# Controller.net
KiCad netlist of a schematic drawn in Altium Designer
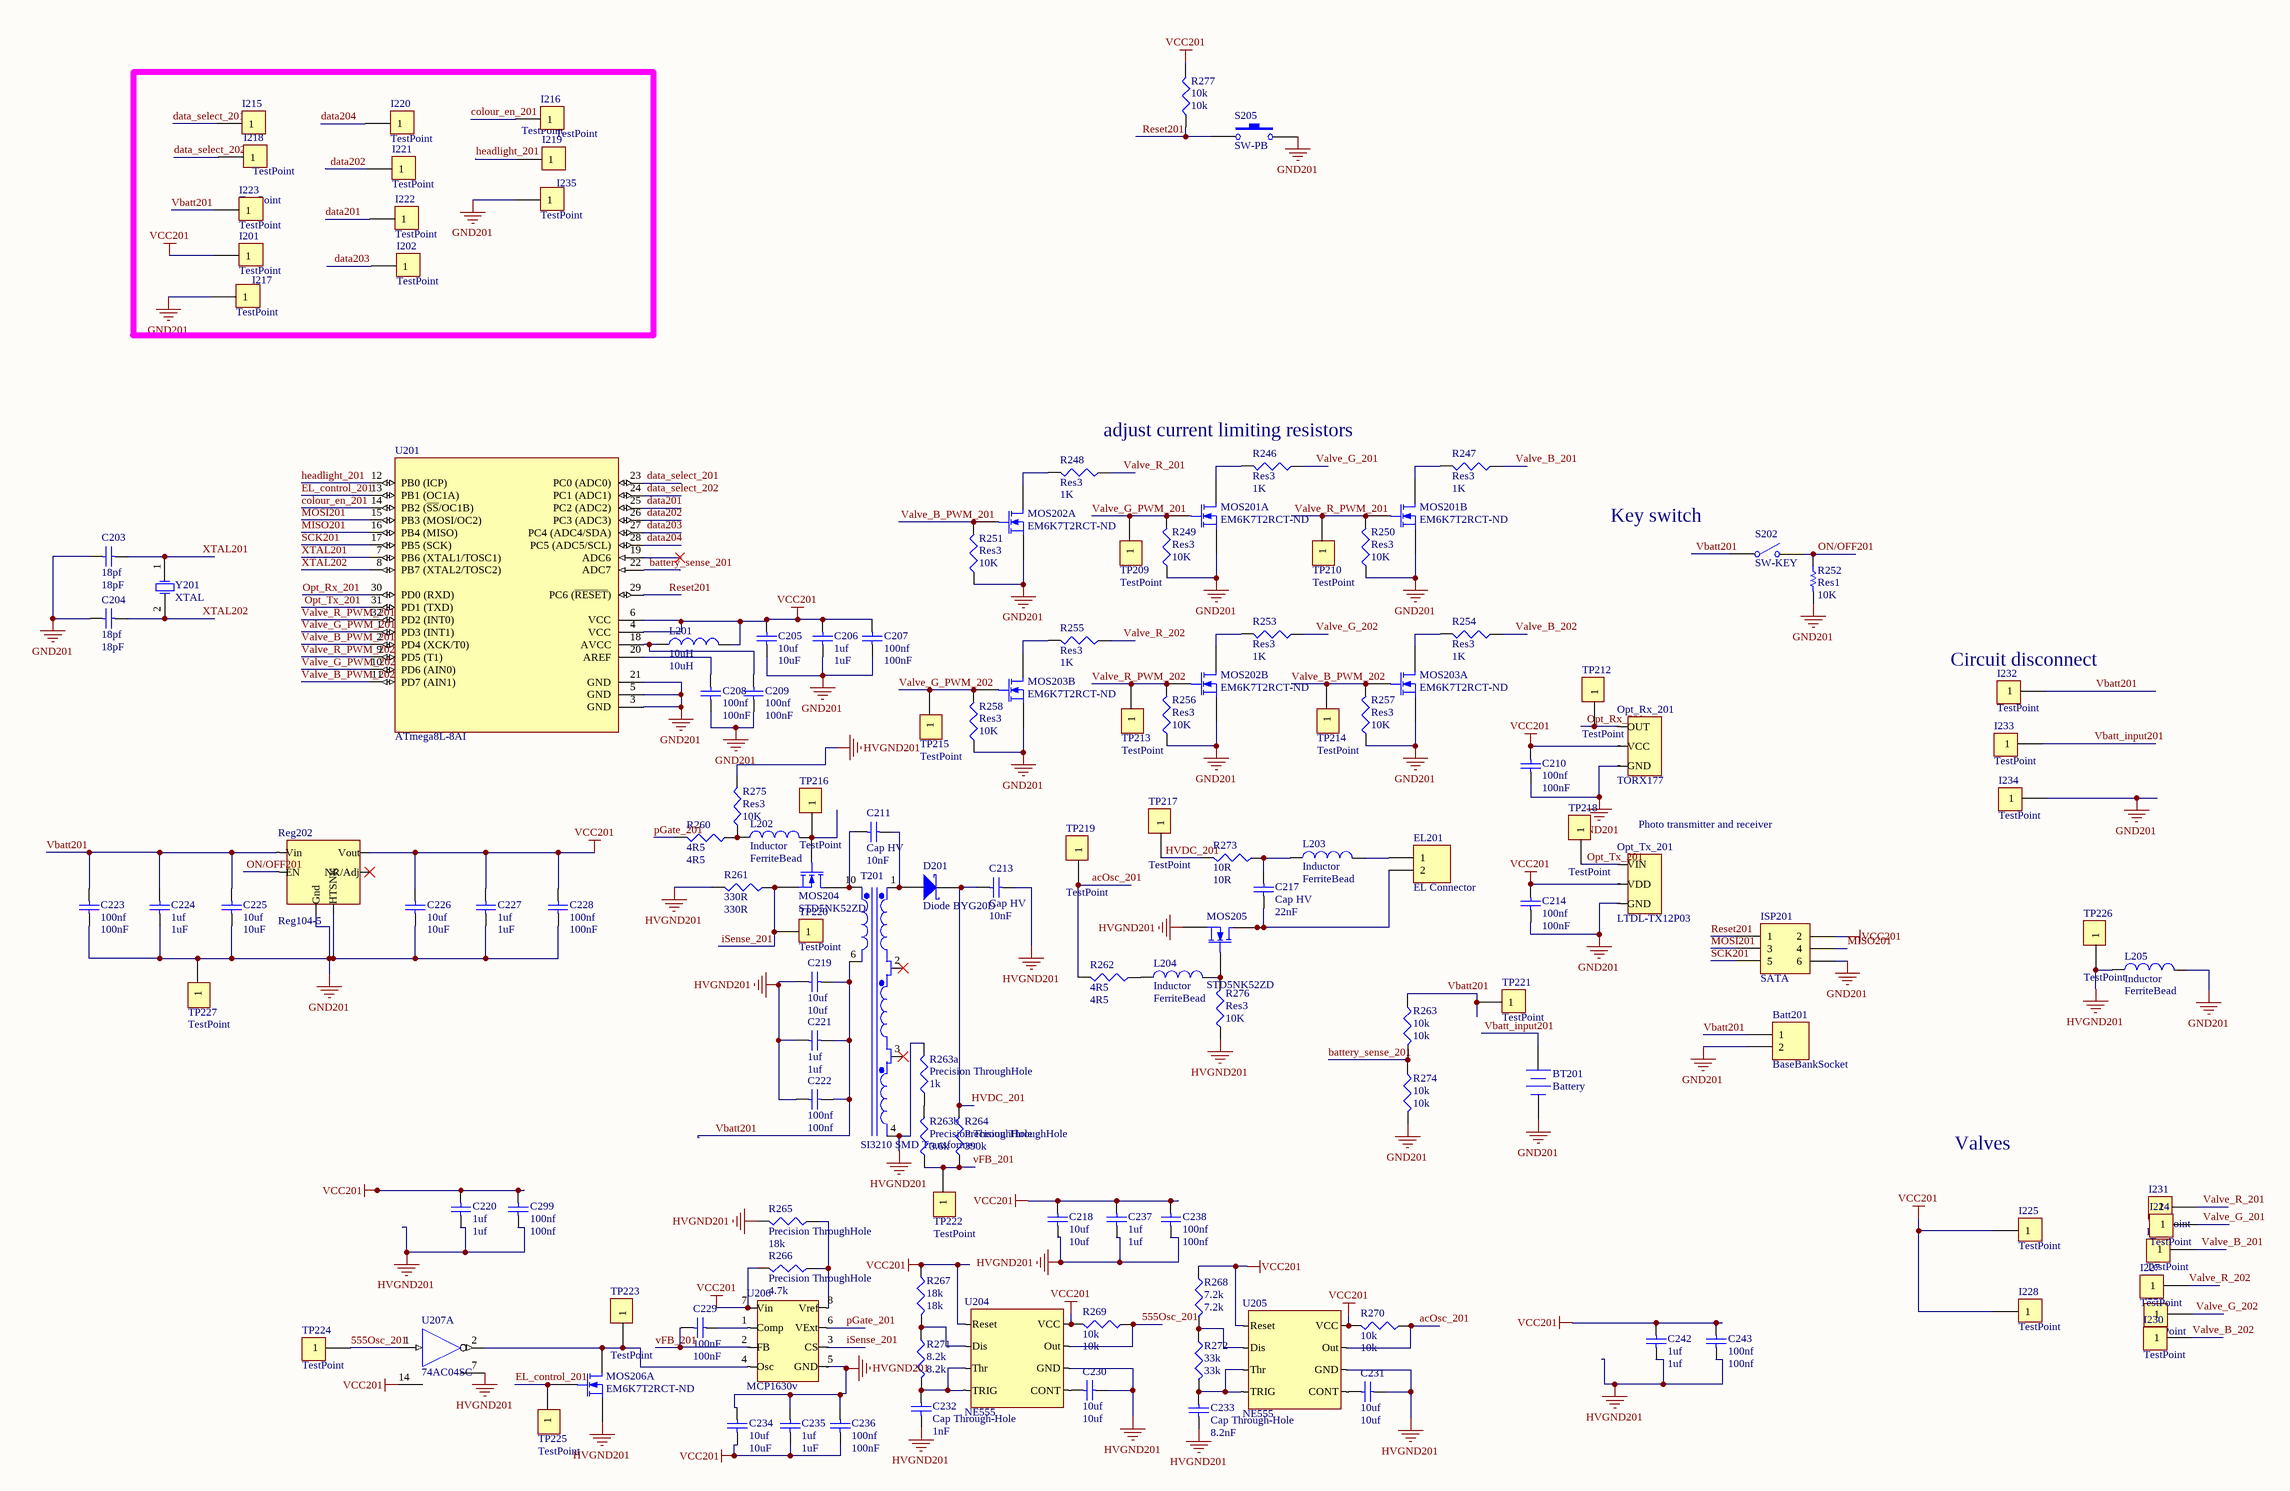
[diagram p0: Controller.SchDoc]

(export (version "E")
  (design (tool "Eeschema 10.0.6"))
  (components
    (comp (ref "Batt201")
      (value "BaseBankSocket")
      (footprint "HDR1X2H")
      (description "Header, 2-Pin")
      (libsource (lib "Miscellaneous Connectors") (part "Header 2"))
    )
    (comp (ref "BT201")
      (value "Battery")
      (footprint "HDR1X2H")
      (description "Multicell Battery")
      (libsource (lib "Miscellaneous Devices") (part "Battery"))
    )
    (comp (ref "C203")
      (value "18pf")
      (footprint "0603")
      (description "Capacitor (Semiconductor SIM Model)")
      (fields (field (name "ALTIUM_VALUE") "18pF"))
      (libsource (lib "Miscellaneous Devices") (part "Cap Semi"))
    )
    (comp (ref "C204")
      (value "18pf")
      (footprint "0603")
      (description "Capacitor (Semiconductor SIM Model)")
      (fields (field (name "ALTIUM_VALUE") "18pF"))
      (libsource (lib "Miscellaneous Devices") (part "Cap Semi"))
    )
    (comp (ref "C205")
      (value "10uf")
      (footprint "0805")
      (description "Capacitor (Semiconductor SIM Model)")
      (fields (field (name "ALTIUM_VALUE") "10uF"))
      (libsource (lib "Miscellaneous Devices") (part "Cap Semi"))
    )
    (comp (ref "C206")
      (value "1uf")
      (footprint "0603")
      (description "Capacitor (Semiconductor SIM Model)")
      (fields (field (name "ALTIUM_VALUE") "1uF"))
      (libsource (lib "Miscellaneous Devices") (part "Cap Semi"))
    )
    (comp (ref "C207")
      (value "100nf")
      (footprint "0603")
      (description "Capacitor (Semiconductor SIM Model)")
      (fields (field (name "ALTIUM_VALUE") "100nF"))
      (libsource (lib "Miscellaneous Devices") (part "Cap Semi"))
    )
    (comp (ref "C208")
      (value "100nf")
      (footprint "0603")
      (description "Capacitor (Semiconductor SIM Model)")
      (fields (field (name "ALTIUM_VALUE") "100nF"))
      (libsource (lib "Miscellaneous Devices") (part "Cap Semi"))
    )
    (comp (ref "C209")
      (value "100nf")
      (footprint "0603")
      (description "Capacitor (Semiconductor SIM Model)")
      (fields (field (name "ALTIUM_VALUE") "100nF"))
      (libsource (lib "Miscellaneous Devices") (part "Cap Semi"))
    )
    (comp (ref "C210")
      (value "100nf")
      (footprint "0603")
      (description "Capacitor (Semiconductor SIM Model)")
      (fields (field (name "ALTIUM_VALUE") "100nF"))
      (libsource (lib "Miscellaneous Devices") (part "Cap Semi"))
    )
    (comp (ref "C211")
      (value "Cap HV")
      (footprint "10n MU Capacitor (HV)")
      (description "Capacitor (Semiconductor SIM Model)")
      (fields (field (name "ALTIUM_VALUE") "10nF"))
      (libsource (lib "Miscellaneous Devices") (part "Cap Semi"))
    )
    (comp (ref "C213")
      (value "Cap HV")
      (footprint "10n MU Capacitor (HV)")
      (description "Capacitor (Semiconductor SIM Model)")
      (fields (field (name "ALTIUM_VALUE") "10nF"))
      (libsource (lib "Miscellaneous Devices") (part "Cap Semi"))
    )
    (comp (ref "C214")
      (value "100nf")
      (footprint "0603")
      (description "Capacitor (Semiconductor SIM Model)")
      (fields (field (name "ALTIUM_VALUE") "100nF"))
      (libsource (lib "Miscellaneous Devices") (part "Cap Semi"))
    )
    (comp (ref "C217")
      (value "Cap HV")
      (footprint "22N MU Capacitor (HV)")
      (description "Capacitor (Semiconductor SIM Model)")
      (fields (field (name "ALTIUM_VALUE") "22nF"))
      (libsource (lib "Miscellaneous Devices") (part "Cap Semi"))
    )
    (comp (ref "C218")
      (value "10uf")
      (footprint "0805")
      (description "Capacitor (Semiconductor SIM Model)")
      (fields (field (name "ALTIUM_VALUE") "10uf"))
      (libsource (lib "Miscellaneous Devices") (part "Cap Semi"))
    )
    (comp (ref "C219")
      (value "10uf")
      (footprint "0805")
      (description "Capacitor (Semiconductor SIM Model)")
      (fields (field (name "ALTIUM_VALUE") "10uf"))
      (libsource (lib "Miscellaneous Devices") (part "Cap Semi"))
    )
    (comp (ref "C220")
      (value "1uf")
      (footprint "0603")
      (description "Capacitor (Semiconductor SIM Model)")
      (fields (field (name "ALTIUM_VALUE") "1uf"))
      (libsource (lib "Miscellaneous Devices") (part "Cap Semi"))
    )
    (comp (ref "C221")
      (value "1uf")
      (footprint "0603")
      (description "Capacitor (Semiconductor SIM Model)")
      (fields (field (name "ALTIUM_VALUE") "1uf"))
      (libsource (lib "Miscellaneous Devices") (part "Cap Semi"))
    )
    (comp (ref "C222")
      (value "100nf")
      (footprint "0603")
      (description "Capacitor (Semiconductor SIM Model)")
      (fields (field (name "ALTIUM_VALUE") "100nf"))
      (libsource (lib "Miscellaneous Devices") (part "Cap Semi"))
    )
    (comp (ref "C223")
      (value "100nf")
      (footprint "0603")
      (description "Capacitor (Semiconductor SIM Model)")
      (fields (field (name "ALTIUM_VALUE") "100nF"))
      (libsource (lib "Miscellaneous Devices") (part "Cap Semi"))
    )
    (comp (ref "C224")
      (value "1uf")
      (footprint "0603")
      (description "Capacitor (Semiconductor SIM Model)")
      (fields (field (name "ALTIUM_VALUE") "1uF"))
      (libsource (lib "Miscellaneous Devices") (part "Cap Semi"))
    )
    (comp (ref "C225")
      (value "10uf")
      (footprint "0805")
      (description "Capacitor (Semiconductor SIM Model)")
      (fields (field (name "ALTIUM_VALUE") "10uF"))
      (libsource (lib "Miscellaneous Devices") (part "Cap Semi"))
    )
    (comp (ref "C226")
      (value "10uf")
      (footprint "0805")
      (description "Capacitor (Semiconductor SIM Model)")
      (fields (field (name "ALTIUM_VALUE") "10uF"))
      (libsource (lib "Miscellaneous Devices") (part "Cap Semi"))
    )
    (comp (ref "C227")
      (value "1uf")
      (footprint "0603")
      (description "Capacitor (Semiconductor SIM Model)")
      (fields (field (name "ALTIUM_VALUE") "1uF"))
      (libsource (lib "Miscellaneous Devices") (part "Cap Semi"))
    )
    (comp (ref "C228")
      (value "100nf")
      (footprint "0603")
      (description "Capacitor (Semiconductor SIM Model)")
      (fields (field (name "ALTIUM_VALUE") "100nF"))
      (libsource (lib "Miscellaneous Devices") (part "Cap Semi"))
    )
    (comp (ref "C229")
      (value "100nF")
      (footprint "0603")
      (description "Capacitor (Semiconductor SIM Model)")
      (fields (field (name "ALTIUM_VALUE") "100nF"))
      (libsource (lib "Miscellaneous Devices") (part "Cap Semi"))
    )
    (comp (ref "C230")
      (value "10uf")
      (footprint "0805")
      (description "Capacitor (Semiconductor SIM Model)")
      (fields (field (name "ALTIUM_VALUE") "10uf"))
      (libsource (lib "Miscellaneous Devices") (part "Cap Semi"))
    )
    (comp (ref "C231")
      (value "10uf")
      (footprint "0805")
      (description "Capacitor (Semiconductor SIM Model)")
      (fields (field (name "ALTIUM_VALUE") "10uf"))
      (libsource (lib "Miscellaneous Devices") (part "Cap Semi"))
    )
    (comp (ref "C232")
      (value "Cap Through-Hole")
      (footprint "Axial 0.4 MU")
      (description "Capacitor (Semiconductor SIM Model)")
      (fields (field (name "ALTIUM_VALUE") "1nF"))
      (libsource (lib "Miscellaneous Devices") (part "Cap Semi"))
    )
    (comp (ref "C233")
      (value "Cap Through-Hole")
      (footprint "Axial 0.4 MU")
      (description "Capacitor (Semiconductor SIM Model)")
      (fields (field (name "ALTIUM_VALUE") "8.2nF"))
      (libsource (lib "Miscellaneous Devices") (part "Cap Semi"))
    )
    (comp (ref "C234")
      (value "10uf")
      (footprint "0805")
      (description "Capacitor (Semiconductor SIM Model)")
      (fields (field (name "ALTIUM_VALUE") "10uF"))
      (libsource (lib "Miscellaneous Devices") (part "Cap Semi"))
    )
    (comp (ref "C235")
      (value "1uf")
      (footprint "0603")
      (description "Capacitor (Semiconductor SIM Model)")
      (fields (field (name "ALTIUM_VALUE") "1uF"))
      (libsource (lib "Miscellaneous Devices") (part "Cap Semi"))
    )
    (comp (ref "C236")
      (value "100nf")
      (footprint "0603")
      (description "Capacitor (Semiconductor SIM Model)")
      (fields (field (name "ALTIUM_VALUE") "100nF"))
      (libsource (lib "Miscellaneous Devices") (part "Cap Semi"))
    )
    (comp (ref "C237")
      (value "1uf")
      (footprint "0603")
      (description "Capacitor (Semiconductor SIM Model)")
      (fields (field (name "ALTIUM_VALUE") "1uf"))
      (libsource (lib "Miscellaneous Devices") (part "Cap Semi"))
    )
    (comp (ref "C238")
      (value "100nf")
      (footprint "0603")
      (description "Capacitor (Semiconductor SIM Model)")
      (fields (field (name "ALTIUM_VALUE") "100nf"))
      (libsource (lib "Miscellaneous Devices") (part "Cap Semi"))
    )
    (comp (ref "C242")
      (value "1uf")
      (footprint "0603")
      (description "Capacitor (Semiconductor SIM Model)")
      (fields (field (name "ALTIUM_VALUE") "1uf"))
      (libsource (lib "Miscellaneous Devices") (part "Cap Semi"))
    )
    (comp (ref "C243")
      (value "100nf")
      (footprint "0603")
      (description "Capacitor (Semiconductor SIM Model)")
      (fields (field (name "ALTIUM_VALUE") "100nf"))
      (libsource (lib "Miscellaneous Devices") (part "Cap Semi"))
    )
    (comp (ref "C299")
      (value "100nf")
      (footprint "0603")
      (description "Capacitor (Semiconductor SIM Model)")
      (fields (field (name "ALTIUM_VALUE") "100nf"))
      (libsource (lib "Miscellaneous Devices") (part "Cap Semi"))
    )
    (comp (ref "D201")
      (value "Diode BYG20D")
      (footprint "BYG20J-E3")
      (description "Schottky Rectifier")
      (libsource (lib "Miscellaneous Devices") (part "Diode 10TQ035"))
    )
    (comp (ref "EL201")
      (value "EL Connector")
      (footprint "HV connector")
      (description "Header, 2-Pin")
      (libsource (lib "Miscellaneous Connectors") (part "Header 2"))
    )
    (comp (ref "I201")
      (value "TestPoint")
      (footprint "TestPoint")
      (libsource (lib "Schlib1") (part "TestPoint"))
    )
    (comp (ref "I202")
      (value "TestPoint")
      (footprint "TestPoint")
      (libsource (lib "Schlib1") (part "TestPoint"))
    )
    (comp (ref "I215")
      (value "TestPoint")
      (footprint "TestPoint")
      (libsource (lib "Schlib1") (part "TestPoint"))
    )
    (comp (ref "I216")
      (value "TestPoint")
      (footprint "TestPoint")
      (libsource (lib "Schlib1") (part "TestPoint"))
    )
    (comp (ref "I217")
      (value "TestPoint")
      (footprint "TestPoint")
      (libsource (lib "Schlib1") (part "TestPoint"))
    )
    (comp (ref "I218")
      (value "TestPoint")
      (footprint "TestPoint")
      (libsource (lib "Schlib1") (part "TestPoint"))
    )
    (comp (ref "I219")
      (value "TestPoint")
      (footprint "TestPoint")
      (libsource (lib "Schlib1") (part "TestPoint"))
    )
    (comp (ref "I220")
      (value "TestPoint")
      (footprint "TestPoint")
      (libsource (lib "Schlib1") (part "TestPoint"))
    )
    (comp (ref "I221")
      (value "TestPoint")
      (footprint "TestPoint")
      (libsource (lib "Schlib1") (part "TestPoint"))
    )
    (comp (ref "I222")
      (value "TestPoint")
      (footprint "TestPoint")
      (libsource (lib "Schlib1") (part "TestPoint"))
    )
    (comp (ref "I223")
      (value "TestPoint")
      (footprint "TestPoint")
      (libsource (lib "Schlib1") (part "TestPoint"))
    )
    (comp (ref "I224") (value "TestPoint") (footprint "TestPoint") (libsource (lib "") (part "TestPoint_1")))
    (comp (ref "I225")
      (value "TestPoint")
      (footprint "TestPoint")
      (libsource (lib "Schlib1") (part "TestPoint"))
    )
    (comp (ref "I226") (value "TestPoint") (footprint "TestPoint") (libsource (lib "") (part "TestPoint_1")))
    (comp (ref "I227") (value "TestPoint") (footprint "TestPoint") (libsource (lib "") (part "TestPoint_1")))
    (comp (ref "I228")
      (value "TestPoint")
      (footprint "TestPoint")
      (libsource (lib "Schlib1") (part "TestPoint"))
    )
    (comp (ref "I229") (value "TestPoint") (footprint "TestPoint") (libsource (lib "") (part "TestPoint_1")))
    (comp (ref "I230") (value "TestPoint") (footprint "TestPoint") (libsource (lib "") (part "TestPoint_1")))
    (comp (ref "I231") (value "TestPoint") (footprint "TestPoint") (libsource (lib "") (part "TestPoint_1")))
    (comp (ref "I232") (value "TestPoint") (footprint "TestPoint") (libsource (lib "") (part "TestPoint_1")))
    (comp (ref "I233") (value "TestPoint") (footprint "TestPoint") (libsource (lib "") (part "TestPoint_1")))
    (comp (ref "I234") (value "TestPoint") (footprint "TestPoint") (libsource (lib "") (part "TestPoint_1")))
    (comp (ref "I235")
      (value "TestPoint")
      (footprint "TestPoint")
      (libsource (lib "Schlib1") (part "TestPoint"))
    )
    (comp (ref "ISP201")
      (value "SATA")
      (footprint "SATA")
      (description "Header, 3-Pin, Dual row")
      (libsource (lib "Miscellaneous Connectors") (part "Header 3X2"))
    )
    (comp (ref "L201")
      (value "10uH")
      (footprint "0805")
      (description "Inductor")
      (fields (field (name "ALTIUM_VALUE") "10uH"))
      (libsource (lib "Miscellaneous Devices") (part "Inductor"))
    )
    (comp (ref "L202")
      (value "Inductor")
      (footprint "Axial 0.4 MU")
      (fields (field (name "ALTIUM_VALUE") "FerriteBead"))
      (libsource (lib "Miscellaneous Devices") (part "Inductor"))
    )
    (comp (ref "L203")
      (value "Inductor")
      (footprint "Axial 0.4 MU")
      (fields (field (name "ALTIUM_VALUE") "FerriteBead"))
      (libsource (lib "Miscellaneous Devices") (part "Inductor"))
    )
    (comp (ref "L204")
      (value "Inductor")
      (footprint "Axial 0.4 MU")
      (fields (field (name "ALTIUM_VALUE") "FerriteBead"))
      (libsource (lib "Miscellaneous Devices") (part "Inductor"))
    )
    (comp (ref "L205")
      (value "Inductor")
      (footprint "Axial 0.4 MU")
      (fields (field (name "ALTIUM_VALUE") "FerriteBead"))
      (libsource (lib "Miscellaneous Devices") (part "Inductor"))
    )
    (comp (ref "MOS201")
      (value "EM6K7T2RCT-ND")
      (footprint "EM6K7T2R-EMT6")
      (libsource (lib "Schlib1") (part "EM6K7T2RCT-ND"))
    )
    (comp (ref "MOS202")
      (value "EM6K7T2RCT-ND")
      (footprint "EM6K7T2R-EMT6")
      (libsource (lib "Schlib1") (part "EM6K7T2RCT-ND"))
    )
    (comp (ref "MOS203")
      (value "EM6K7T2RCT-ND")
      (footprint "EM6K7T2R-EMT6")
      (libsource (lib "Schlib1") (part "EM6K7T2RCT-ND"))
    )
    (comp (ref "MOS204")
      (value "STD5NK52ZD")
      (footprint "DPAK")
      (description "N-Channel MOSFET")
      (libsource (lib "Miscellaneous Devices") (part "MOSFET-N"))
    )
    (comp (ref "MOS205")
      (value "STD5NK52ZD")
      (footprint "DPAK")
      (description "N-Channel MOSFET")
      (libsource (lib "Miscellaneous Devices") (part "MOSFET-N"))
    )
    (comp (ref "MOS206")
      (value "EM6K7T2RCT-ND")
      (footprint "EM6K7T2R-EMT6")
      (libsource (lib "") (part "EM6K7T2RCT-ND_1"))
    )
    (comp (ref "Opt_Rx_201")
      (value "TORX177")
      (footprint "Optical RX")
      (description "Optical receiver module")
      (libsource (lib "Schlib1") (part "TORX177"))
    )
    (comp (ref "Opt_Tx_201")
      (value "LTDL-TX12P03")
      (footprint "Optical TX")
      (description "Optical transmitter")
      (libsource (lib "Schlib1") (part "LTDL-TX12P03"))
    )
    (comp (ref "R246")
      (value "Res3")
      (footprint "0805")
      (description "Resistor")
      (fields (field (name "ALTIUM_VALUE") "1K"))
      (libsource (lib "Miscellaneous Devices") (part "Res3"))
    )
    (comp (ref "R247")
      (value "Res3")
      (footprint "0805")
      (description "Resistor")
      (fields (field (name "ALTIUM_VALUE") "1K"))
      (libsource (lib "Miscellaneous Devices") (part "Res3"))
    )
    (comp (ref "R248")
      (value "Res3")
      (footprint "0805")
      (description "Resistor")
      (fields (field (name "ALTIUM_VALUE") "1K"))
      (libsource (lib "Miscellaneous Devices") (part "Res3"))
    )
    (comp (ref "R249")
      (value "Res3")
      (footprint "0805")
      (description "Resistor")
      (fields (field (name "ALTIUM_VALUE") "10K"))
      (libsource (lib "Miscellaneous Devices") (part "Res3"))
    )
    (comp (ref "R250")
      (value "Res3")
      (footprint "0805")
      (description "Resistor")
      (fields (field (name "ALTIUM_VALUE") "10K"))
      (libsource (lib "Miscellaneous Devices") (part "Res3"))
    )
    (comp (ref "R251")
      (value "Res3")
      (footprint "0805")
      (description "Resistor")
      (fields (field (name "ALTIUM_VALUE") "10K"))
      (libsource (lib "Miscellaneous Devices") (part "Res3"))
    )
    (comp (ref "R252")
      (value "Res1")
      (footprint "0805")
      (description "Resistor")
      (fields (field (name "ALTIUM_VALUE") "10K"))
      (libsource (lib "Miscellaneous Devices") (part "Res1"))
    )
    (comp (ref "R253")
      (value "Res3")
      (footprint "0805")
      (description "Resistor")
      (fields (field (name "ALTIUM_VALUE") "1K"))
      (libsource (lib "Miscellaneous Devices") (part "Res3"))
    )
    (comp (ref "R254")
      (value "Res3")
      (footprint "0805")
      (description "Resistor")
      (fields (field (name "ALTIUM_VALUE") "1K"))
      (libsource (lib "Miscellaneous Devices") (part "Res3"))
    )
    (comp (ref "R255")
      (value "Res3")
      (footprint "0805")
      (description "Resistor")
      (fields (field (name "ALTIUM_VALUE") "1K"))
      (libsource (lib "Miscellaneous Devices") (part "Res3"))
    )
    (comp (ref "R256")
      (value "Res3")
      (footprint "0805")
      (description "Resistor")
      (fields (field (name "ALTIUM_VALUE") "10K"))
      (libsource (lib "Miscellaneous Devices") (part "Res3"))
    )
    (comp (ref "R257")
      (value "Res3")
      (footprint "0805")
      (description "Resistor")
      (fields (field (name "ALTIUM_VALUE") "10K"))
      (libsource (lib "Miscellaneous Devices") (part "Res3"))
    )
    (comp (ref "R258")
      (value "Res3")
      (footprint "0805")
      (description "Resistor")
      (fields (field (name "ALTIUM_VALUE") "10K"))
      (libsource (lib "Miscellaneous Devices") (part "Res3"))
    )
    (comp (ref "R260")
      (value "4R5")
      (footprint "0805")
      (description "Resistor")
      (fields (field (name "ALTIUM_VALUE") "4R5"))
      (libsource (lib "Miscellaneous Devices") (part "Res3"))
    )
    (comp (ref "R261")
      (value "330R")
      (footprint "0805")
      (description "Resistor")
      (fields (field (name "ALTIUM_VALUE") "330R"))
      (libsource (lib "Miscellaneous Devices") (part "Res3"))
    )
    (comp (ref "R262")
      (value "4R5")
      (footprint "0805")
      (description "Resistor")
      (fields (field (name "ALTIUM_VALUE") "4R5"))
      (libsource (lib "Miscellaneous Devices") (part "Res3"))
    )
    (comp (ref "R263")
      (value "10k")
      (footprint "0603")
      (description "Resistor")
      (fields (field (name "ALTIUM_VALUE") "10k"))
      (libsource (lib "Miscellaneous Devices") (part "Res3"))
    )
    (comp (ref "R263a")
      (value "Precision ThroughHole")
      (footprint "Axial 0.4 MU")
      (description "Resistor")
      (fields (field (name "ALTIUM_VALUE") "1k"))
      (libsource (lib "Miscellaneous Devices") (part "Res3"))
    )
    (comp (ref "R263b")
      (value "Precision ThroughHole")
      (footprint "Axial 0.4 MU")
      (description "Resistor")
      (fields (field (name "ALTIUM_VALUE") "3.6k"))
      (libsource (lib "Miscellaneous Devices") (part "Res3"))
    )
    (comp (ref "R264")
      (value "Precision ThroughHole")
      (footprint "Axial 0.4 MU")
      (description "Resistor")
      (fields (field (name "ALTIUM_VALUE") "390k"))
      (libsource (lib "Miscellaneous Devices") (part "Res3"))
    )
    (comp (ref "R265")
      (value "Precision ThroughHole")
      (footprint "Axial 0.4 MU")
      (description "Resistor")
      (fields (field (name "ALTIUM_VALUE") "18k"))
      (libsource (lib "Miscellaneous Devices") (part "Res3"))
    )
    (comp (ref "R266")
      (value "Precision ThroughHole")
      (footprint "Axial 0.4 MU")
      (description "Resistor")
      (fields (field (name "ALTIUM_VALUE") "4.7k"))
      (libsource (lib "Miscellaneous Devices") (part "Res3"))
    )
    (comp (ref "R267")
      (value "18k")
      (footprint "0603")
      (description "Resistor")
      (fields (field (name "ALTIUM_VALUE") "18k"))
      (libsource (lib "Miscellaneous Devices") (part "Res3"))
    )
    (comp (ref "R268")
      (value "7.2k")
      (footprint "0805")
      (description "Resistor")
      (fields (field (name "ALTIUM_VALUE") "7.2k"))
      (libsource (lib "Miscellaneous Devices") (part "Res3"))
    )
    (comp (ref "R269")
      (value "10k")
      (footprint "0603")
      (description "Resistor")
      (fields (field (name "ALTIUM_VALUE") "10k"))
      (libsource (lib "Miscellaneous Devices") (part "Res3"))
    )
    (comp (ref "R270")
      (value "10k")
      (footprint "0603")
      (description "Resistor")
      (fields (field (name "ALTIUM_VALUE") "10k"))
      (libsource (lib "Miscellaneous Devices") (part "Res3"))
    )
    (comp (ref "R271")
      (value "8.2k")
      (footprint "0805")
      (description "Resistor")
      (fields (field (name "ALTIUM_VALUE") "8.2k"))
      (libsource (lib "Miscellaneous Devices") (part "Res3"))
    )
    (comp (ref "R272")
      (value "33k")
      (footprint "0805")
      (description "Resistor")
      (fields (field (name "ALTIUM_VALUE") "33k"))
      (libsource (lib "Miscellaneous Devices") (part "Res3"))
    )
    (comp (ref "R273")
      (value "10R")
      (footprint "0805")
      (description "Resistor")
      (fields (field (name "ALTIUM_VALUE") "10R"))
      (libsource (lib "Miscellaneous Devices") (part "Res3"))
    )
    (comp (ref "R274")
      (value "10k")
      (footprint "0603")
      (description "Resistor")
      (fields (field (name "ALTIUM_VALUE") "10k"))
      (libsource (lib "Miscellaneous Devices") (part "Res3"))
    )
    (comp (ref "R275")
      (value "Res3")
      (footprint "0805")
      (description "Resistor")
      (fields (field (name "ALTIUM_VALUE") "10K"))
      (libsource (lib "Miscellaneous Devices") (part "Res3"))
    )
    (comp (ref "R276")
      (value "Res3")
      (footprint "0805")
      (description "Resistor")
      (fields (field (name "ALTIUM_VALUE") "10K"))
      (libsource (lib "Miscellaneous Devices") (part "Res3"))
    )
    (comp (ref "R277")
      (value "10k")
      (footprint "0603")
      (description "Resistor")
      (fields (field (name "ALTIUM_VALUE") "10k"))
      (libsource (lib "Miscellaneous Devices") (part "Res3"))
    )
    (comp (ref "Reg202")
      (value "Reg104-5")
      (footprint "REG104-5-DDPAK5")
      (libsource (lib "Schlib1") (part "Reg104-5"))
    )
    (comp (ref "S202")
      (value "SW-KEY")
      (footprint "2 pin switch (surface mount)")
      (description "Single-Pole, Single-Throw Switch")
      (libsource (lib "Miscellaneous Devices") (part "SW-SPST"))
    )
    (comp (ref "S205")
      (value "SW-PB")
      (footprint "2 pin switch (surface mount)")
      (description "Switch")
      (libsource (lib "Miscellaneous Devices") (part "SW-PB"))
    )
    (comp (ref "T201")
      (value "SI3210 SMD Transformer")
      (footprint "SI3210 SMD Transformer")
      (libsource (lib "Schlib1") (part "SI3210 SMD Transformer"))
    )
    (comp (ref "TP209") (value "TestPoint") (footprint "TestPoint") (libsource (lib "") (part "TestPoint_2")))
    (comp (ref "TP210") (value "TestPoint") (footprint "TestPoint") (libsource (lib "") (part "TestPoint_2")))
    (comp (ref "TP212") (value "TestPoint") (footprint "TestPoint") (libsource (lib "") (part "TestPoint_3")))
    (comp (ref "TP213") (value "TestPoint") (footprint "TestPoint") (libsource (lib "") (part "TestPoint_2")))
    (comp (ref "TP214") (value "TestPoint") (footprint "TestPoint") (libsource (lib "") (part "TestPoint_2")))
    (comp (ref "TP215") (value "TestPoint") (footprint "TestPoint") (libsource (lib "") (part "TestPoint_2")))
    (comp (ref "TP216") (value "TestPoint") (footprint "TestPoint") (libsource (lib "") (part "TestPoint_3")))
    (comp (ref "TP217") (value "TestPoint") (footprint "TestPoint") (libsource (lib "") (part "TestPoint_3")))
    (comp (ref "TP218") (value "TestPoint") (footprint "TestPoint") (libsource (lib "") (part "TestPoint_3")))
    (comp (ref "TP219") (value "TestPoint") (footprint "TestPoint") (libsource (lib "") (part "TestPoint_3")))
    (comp (ref "TP220")
      (value "TestPoint")
      (footprint "TestPoint")
      (libsource (lib "Schlib1") (part "TestPoint"))
    )
    (comp (ref "TP221")
      (value "TestPoint")
      (footprint "TestPoint")
      (libsource (lib "Schlib1") (part "TestPoint"))
    )
    (comp (ref "TP222") (value "TestPoint") (footprint "TestPoint") (libsource (lib "") (part "TestPoint_2")))
    (comp (ref "TP223") (value "TestPoint") (footprint "TestPoint") (libsource (lib "") (part "TestPoint_3")))
    (comp (ref "TP224") (value "TestPoint") (footprint "TestPoint") (libsource (lib "") (part "TestPoint_1")))
    (comp (ref "TP225") (value "TestPoint") (footprint "TestPoint") (libsource (lib "") (part "TestPoint_2")))
    (comp (ref "TP226") (value "TestPoint") (footprint "TestPoint") (libsource (lib "") (part "TestPoint_3")))
    (comp (ref "TP227") (value "TestPoint") (footprint "TestPoint") (libsource (lib "") (part "TestPoint_2")))
    (comp (ref "U201")
      (value "ATmega8L-8AI")
      (footprint "ATMega_GOOD")
      (description "8-Bit AVR Microcontroller with 8K Bytes of In-System Programmable Flash Memory")
      (libsource (lib "Atmel Microcontroller 8-Bit AVR") (part "ATmega8L-8AI"))
    )
    (comp (ref "U204") (value "NE555") (footprint "NE555") (libsource (lib "Schlib1") (part "NE555")))
    (comp (ref "U205") (value "NE555") (footprint "NE555") (libsource (lib "Schlib1") (part "NE555")))
    (comp (ref "U206")
      (value "MCP1630v")
      (footprint "8MSOP (MCP Alternative)")
      (libsource (lib "Schlib1") (part "MCP1630v"))
    )
    (comp (ref "U207")
      (value "74AC04SC")
      (footprint "74AC04SC 14-SOIC")
      (description "Hex Inverter")
      (libsource (lib "TI Logic Gate 1") (part "SN54HC04J"))
    )
    (comp (ref "Y201")
      (value "XTAL")
      (footprint "ABLS-16MHz-B4-T")
      (description "Crystal Oscillator")
      (libsource (lib "Miscellaneous Devices") (part "XTAL"))
    )
  )
  (nets
    (net (code "1") (name "/555Osc_201") (class "Default")
      (node (ref "R269") (pin "1") (pinfunction "1_1") (pintype "passive"))
      (node (ref "TP224") (pin "1") (pinfunction "1_1") (pintype "passive"))
      (node (ref "U204") (pin "3") (pinfunction "Out_3") (pintype "passive"))
      (node (ref "U207") (pin "1") (pinfunction "A_1") (pintype "input"))
    )
    (net (code "2") (name "/EL_control_201") (class "Default")
      (node (ref "MOS206") (pin "2") (pinfunction "G_2") (pintype "passive"))
      (node (ref "TP225") (pin "1") (pinfunction "1_1") (pintype "passive"))
      (node (ref "U201") (pin "13") (pinfunction "PB1_(OC1A)_13") (pintype "bidirectional"))
    )
    (net (code "3") (name "/HVDC_201") (class "Default")
      (node (ref "C213") (pin "2") (pinfunction "2_2") (pintype "passive"))
      (node (ref "D201") (pin "1") (pinfunction "K_1") (pintype "passive"))
      (node (ref "R264") (pin "2") (pinfunction "2_2") (pintype "passive"))
      (node (ref "R273") (pin "1") (pinfunction "1_1") (pintype "passive"))
      (node (ref "TP217") (pin "1") (pinfunction "1_1") (pintype "passive"))
    )
    (net (code "4") (name "/MISO201") (class "Default")
      (node (ref "ISP201") (pin "4") (pinfunction "4_4") (pintype "passive"))
      (node (ref "U201") (pin "16") (pinfunction "PB4_(MISO)_16") (pintype "bidirectional"))
    )
    (net (code "5") (name "/MOSI201") (class "Default")
      (node (ref "ISP201") (pin "3") (pinfunction "3_3") (pintype "passive"))
      (node (ref "U201") (pin "15") (pinfunction "PB3_(MOSI/OC2)_15") (pintype "bidirectional"))
    )
    (net (code "6") (name "/ON{slash}OFF201") (class "Default")
      (node (ref "R252") (pin "1") (pinfunction "1_1") (pintype "passive"))
      (node (ref "Reg202") (pin "5") (pinfunction "EN_5") (pintype "passive"))
      (node (ref "S202") (pin "2") (pinfunction "NO_2") (pintype "passive"))
    )
    (net (code "7") (name "/Opt_Rx_201") (class "Default")
      (node (ref "Opt_Rx_201") (pin "1") (pinfunction "OUT_1") (pintype "passive"))
      (node (ref "TP212") (pin "1") (pinfunction "1_1") (pintype "passive"))
      (node (ref "U201") (pin "30") (pinfunction "PD0_(RXD)_30") (pintype "bidirectional"))
    )
    (net (code "8") (name "/Opt_Tx_201") (class "Default")
      (node (ref "Opt_Tx_201") (pin "1") (pinfunction "VIN_1") (pintype "passive"))
      (node (ref "TP218") (pin "1") (pinfunction "1_1") (pintype "passive"))
      (node (ref "U201") (pin "31") (pinfunction "PD1_(TXD)_31") (pintype "bidirectional"))
    )
    (net (code "9") (name "/Reset201") (class "Default")
      (node (ref "ISP201") (pin "1") (pinfunction "1_1") (pintype "passive"))
      (node (ref "R277") (pin "1") (pinfunction "1_1") (pintype "passive"))
      (node (ref "S205") (pin "1") (pinfunction "1_1") (pintype "passive"))
      (node (ref "U201") (pin "29") (pinfunction "PC6_(~{RESET})_29") (pintype "bidirectional"))
    )
    (net (code "10") (name "/SCK201") (class "Default")
      (node (ref "ISP201") (pin "5") (pinfunction "5_5") (pintype "passive"))
      (node (ref "U201") (pin "17") (pinfunction "PB5_(SCK)_17") (pintype "bidirectional"))
    )
    (net (code "11") (name "/Valve_B_201") (class "Default")
      (node (ref "I226") (pin "1") (pinfunction "1_1") (pintype "passive"))
      (node (ref "R247") (pin "1") (pinfunction "1_1") (pintype "passive"))
    )
    (net (code "12") (name "/Valve_B_202") (class "Default")
      (node (ref "I230") (pin "1") (pinfunction "1_1") (pintype "passive"))
      (node (ref "R254") (pin "1") (pinfunction "1_1") (pintype "passive"))
    )
    (net (code "13") (name "/Valve_B_PWM_201") (class "Default")
      (node (ref "MOS202") (pin "2") (pinfunction "G_2") (pintype "passive"))
      (node (ref "R251") (pin "2") (pinfunction "2_2") (pintype "passive"))
      (node (ref "U201") (pin "2") (pinfunction "PD4_(XCK/T0)_2") (pintype "bidirectional"))
    )
    (net (code "14") (name "/Valve_B_PWM_202") (class "Default")
      (node (ref "MOS203") (pin "2") (pinfunction "G_2") (pintype "passive"))
      (node (ref "R257") (pin "2") (pinfunction "2_2") (pintype "passive"))
      (node (ref "TP214") (pin "1") (pinfunction "1_1") (pintype "passive"))
      (node (ref "U201") (pin "11") (pinfunction "PD7_(AIN1)_11") (pintype "bidirectional"))
    )
    (net (code "15") (name "/Valve_G_201") (class "Default")
      (node (ref "I224") (pin "1") (pinfunction "1_1") (pintype "passive"))
      (node (ref "R246") (pin "1") (pinfunction "1_1") (pintype "passive"))
    )
    (net (code "16") (name "/Valve_G_202") (class "Default")
      (node (ref "I229") (pin "1") (pinfunction "1_1") (pintype "passive"))
      (node (ref "R253") (pin "1") (pinfunction "1_1") (pintype "passive"))
    )
    (net (code "17") (name "/Valve_G_PWM_201") (class "Default")
      (node (ref "MOS201") (pin "2") (pinfunction "G_2") (pintype "passive"))
      (node (ref "R249") (pin "2") (pinfunction "2_2") (pintype "passive"))
      (node (ref "TP209") (pin "1") (pinfunction "1_1") (pintype "passive"))
      (node (ref "U201") (pin "1") (pinfunction "PD3_(INT1)_1") (pintype "bidirectional"))
    )
    (net (code "18") (name "/Valve_G_PWM_202") (class "Default")
      (node (ref "MOS203") (pin "5") (pinfunction "G_5") (pintype "passive"))
      (node (ref "R258") (pin "2") (pinfunction "2_2") (pintype "passive"))
      (node (ref "TP215") (pin "1") (pinfunction "1_1") (pintype "passive"))
      (node (ref "U201") (pin "10") (pinfunction "PD6_(AIN0)_10") (pintype "bidirectional"))
    )
    (net (code "19") (name "/Valve_R_201") (class "Default")
      (node (ref "I231") (pin "1") (pinfunction "1_1") (pintype "passive"))
      (node (ref "R248") (pin "1") (pinfunction "1_1") (pintype "passive"))
    )
    (net (code "20") (name "/Valve_R_202") (class "Default")
      (node (ref "I227") (pin "1") (pinfunction "1_1") (pintype "passive"))
      (node (ref "R255") (pin "1") (pinfunction "1_1") (pintype "passive"))
    )
    (net (code "21") (name "/Valve_R_PWM_201") (class "Default")
      (node (ref "MOS201") (pin "5") (pinfunction "G_5") (pintype "passive"))
      (node (ref "R250") (pin "2") (pinfunction "2_2") (pintype "passive"))
      (node (ref "TP210") (pin "1") (pinfunction "1_1") (pintype "passive"))
      (node (ref "U201") (pin "32") (pinfunction "PD2_(INT0)_32") (pintype "bidirectional"))
    )
    (net (code "22") (name "/Valve_R_PWM_202") (class "Default")
      (node (ref "MOS202") (pin "5") (pinfunction "G_5") (pintype "passive"))
      (node (ref "R256") (pin "2") (pinfunction "2_2") (pintype "passive"))
      (node (ref "TP213") (pin "1") (pinfunction "1_1") (pintype "passive"))
      (node (ref "U201") (pin "9") (pinfunction "PD5_(T1)_9") (pintype "bidirectional"))
    )
    (net (code "23") (name "/Vbatt201") (class "Default")
      (node (ref "Batt201") (pin "1") (pinfunction "1_1") (pintype "passive"))
      (node (ref "C219") (pin "1") (pinfunction "1_1") (pintype "passive"))
      (node (ref "C221") (pin "1") (pinfunction "1_1") (pintype "passive"))
      (node (ref "C222") (pin "1") (pinfunction "1_1") (pintype "passive"))
      (node (ref "C223") (pin "2") (pinfunction "2_2") (pintype "passive"))
      (node (ref "C224") (pin "2") (pinfunction "2_2") (pintype "passive"))
      (node (ref "C225") (pin "2") (pinfunction "2_2") (pintype "passive"))
      (node (ref "I223") (pin "1") (pinfunction "1_1") (pintype "passive"))
      (node (ref "I232") (pin "1") (pinfunction "1_1") (pintype "passive"))
      (node (ref "R263") (pin "1") (pinfunction "1_1") (pintype "passive"))
      (node (ref "Reg202") (pin "1") (pinfunction "Vin_1") (pintype "passive"))
      (node (ref "S202") (pin "1") (pinfunction "COMMON_1") (pintype "passive"))
      (node (ref "T201") (pin "6") (pinfunction "Pri-_6") (pintype "passive"))
      (node (ref "TP221") (pin "1") (pinfunction "1_1") (pintype "passive"))
    )
    (net (code "24") (name "/Vbatt_input201") (class "Default")
      (node (ref "BT201") (pin "1") (pinfunction "+_1") (pintype "passive"))
      (node (ref "I233") (pin "1") (pinfunction "1_1") (pintype "passive"))
    )
    (net (code "25") (name "/XTAL201") (class "Default")
      (node (ref "C203") (pin "2") (pinfunction "2_2") (pintype "passive"))
      (node (ref "U201") (pin "7") (pinfunction "PB6_(XTAL1/TOSC1)_7") (pintype "bidirectional"))
      (node (ref "Y201") (pin "1") (pinfunction "OSC1_1") (pintype "passive"))
    )
    (net (code "26") (name "/XTAL202") (class "Default")
      (node (ref "C204") (pin "2") (pinfunction "2_2") (pintype "passive"))
      (node (ref "U201") (pin "8") (pinfunction "PB7_(XTAL2/TOSC2)_8") (pintype "bidirectional"))
      (node (ref "Y201") (pin "2") (pinfunction "OSC2_2") (pintype "passive"))
    )
    (net (code "27") (name "/acOsc_201") (class "Default")
      (node (ref "R262") (pin "2") (pinfunction "2_2") (pintype "passive"))
      (node (ref "R270") (pin "1") (pinfunction "1_1") (pintype "passive"))
      (node (ref "TP219") (pin "1") (pinfunction "1_1") (pintype "passive"))
      (node (ref "U205") (pin "3") (pinfunction "Out_3") (pintype "passive"))
    )
    (net (code "28") (name "/battery_sense_201") (class "Default")
      (node (ref "R263") (pin "2") (pinfunction "2_2") (pintype "passive"))
      (node (ref "R274") (pin "1") (pinfunction "1_1") (pintype "passive"))
      (node (ref "U201") (pin "22") (pinfunction "ADC7_22") (pintype "input"))
    )
    (net (code "29") (name "/colour_en_201") (class "Default")
      (node (ref "I216") (pin "1") (pinfunction "1_1") (pintype "passive"))
      (node (ref "U201") (pin "14") (pinfunction "PB2_(~{SS}/OC1B)_14") (pintype "bidirectional"))
    )
    (net (code "30") (name "/data201") (class "Default")
      (node (ref "I222") (pin "1") (pinfunction "1_1") (pintype "passive"))
      (node (ref "U201") (pin "25") (pinfunction "PC2_(ADC2)_25") (pintype "bidirectional"))
    )
    (net (code "31") (name "/data202") (class "Default")
      (node (ref "I221") (pin "1") (pinfunction "1_1") (pintype "passive"))
      (node (ref "U201") (pin "26") (pinfunction "PC3_(ADC3)_26") (pintype "bidirectional"))
    )
    (net (code "32") (name "/data203") (class "Default")
      (node (ref "I202") (pin "1") (pinfunction "1_1") (pintype "passive"))
      (node (ref "U201") (pin "27") (pinfunction "PC4_(ADC4/SDA)_27") (pintype "bidirectional"))
    )
    (net (code "33") (name "/data204") (class "Default")
      (node (ref "I220") (pin "1") (pinfunction "1_1") (pintype "passive"))
      (node (ref "U201") (pin "28") (pinfunction "PC5_(ADC5/SCL)_28") (pintype "bidirectional"))
    )
    (net (code "34") (name "/data_select_201") (class "Default")
      (node (ref "I215") (pin "1") (pinfunction "1_1") (pintype "passive"))
      (node (ref "U201") (pin "23") (pinfunction "PC0_(ADC0)_23") (pintype "bidirectional"))
    )
    (net (code "35") (name "/data_select_202") (class "Default")
      (node (ref "I218") (pin "1") (pinfunction "1_1") (pintype "passive"))
      (node (ref "U201") (pin "24") (pinfunction "PC1_(ADC1)_24") (pintype "bidirectional"))
    )
    (net (code "36") (name "/headlight_201") (class "Default")
      (node (ref "I219") (pin "1") (pinfunction "1_1") (pintype "passive"))
      (node (ref "U201") (pin "12") (pinfunction "PB0_(ICP)_12") (pintype "bidirectional"))
    )
    (net (code "37") (name "/iSense_201") (class "Default")
      (node (ref "MOS204") (pin "3") (pinfunction "S_3") (pintype "passive"))
      (node (ref "R261") (pin "1") (pinfunction "1_1") (pintype "passive"))
      (node (ref "TP220") (pin "1") (pinfunction "1_1") (pintype "passive"))
      (node (ref "U206") (pin "3") (pinfunction "CS_3") (pintype "passive"))
    )
    (net (code "38") (name "/pGate_201") (class "Default")
      (node (ref "R260") (pin "2") (pinfunction "2_2") (pintype "passive"))
      (node (ref "U206") (pin "6") (pinfunction "VExt_6") (pintype "passive"))
    )
    (net (code "39") (name "/vFB_201") (class "Default")
      (node (ref "C229") (pin "2") (pinfunction "2_2") (pintype "passive"))
      (node (ref "R263b") (pin "1") (pinfunction "1_1") (pintype "passive"))
      (node (ref "R264") (pin "1") (pinfunction "1_1") (pintype "passive"))
      (node (ref "TP222") (pin "1") (pinfunction "1_1") (pintype "passive"))
      (node (ref "U206") (pin "2") (pinfunction "FB_2") (pintype "passive"))
    )
    (net (code "40") (name "GND201") (class "Default")
      (node (ref "BT201") (pin "2") (pinfunction "-_2") (pintype "passive"))
      (node (ref "Batt201") (pin "2") (pinfunction "2_2") (pintype "passive"))
      (node (ref "C203") (pin "1") (pinfunction "1_1") (pintype "passive"))
      (node (ref "C204") (pin "1") (pinfunction "1_1") (pintype "passive"))
      (node (ref "C205") (pin "1") (pinfunction "1_1") (pintype "passive"))
      (node (ref "C206") (pin "1") (pinfunction "1_1") (pintype "passive"))
      (node (ref "C207") (pin "1") (pinfunction "1_1") (pintype "passive"))
      (node (ref "C208") (pin "1") (pinfunction "1_1") (pintype "passive"))
      (node (ref "C209") (pin "1") (pinfunction "1_1") (pintype "passive"))
      (node (ref "C210") (pin "1") (pinfunction "1_1") (pintype "passive"))
      (node (ref "C214") (pin "1") (pinfunction "1_1") (pintype "passive"))
      (node (ref "C223") (pin "1") (pinfunction "1_1") (pintype "passive"))
      (node (ref "C224") (pin "1") (pinfunction "1_1") (pintype "passive"))
      (node (ref "C225") (pin "1") (pinfunction "1_1") (pintype "passive"))
      (node (ref "C226") (pin "1") (pinfunction "1_1") (pintype "passive"))
      (node (ref "C227") (pin "1") (pinfunction "1_1") (pintype "passive"))
      (node (ref "C228") (pin "1") (pinfunction "1_1") (pintype "passive"))
      (node (ref "I217") (pin "1") (pinfunction "1_1") (pintype "passive"))
      (node (ref "I234") (pin "1") (pinfunction "1_1") (pintype "passive"))
      (node (ref "I235") (pin "1") (pinfunction "1_1") (pintype "passive"))
      (node (ref "ISP201") (pin "6") (pinfunction "6_6") (pintype "passive"))
      (node (ref "L205") (pin "2") (pinfunction "2_2") (pintype "passive"))
      (node (ref "MOS201") (pin "1") (pinfunction "S_1") (pintype "passive"))
      (node (ref "MOS201") (pin "4") (pinfunction "S_4") (pintype "passive"))
      (node (ref "MOS202") (pin "1") (pinfunction "S_1") (pintype "passive"))
      (node (ref "MOS202") (pin "4") (pinfunction "S_4") (pintype "passive"))
      (node (ref "MOS203") (pin "1") (pinfunction "S_1") (pintype "passive"))
      (node (ref "MOS203") (pin "4") (pinfunction "S_4") (pintype "passive"))
      (node (ref "Opt_Rx_201") (pin "2") (pinfunction "GND_2") (pintype "passive"))
      (node (ref "Opt_Tx_201") (pin "3") (pinfunction "GND_3") (pintype "passive"))
      (node (ref "R249") (pin "1") (pinfunction "1_1") (pintype "passive"))
      (node (ref "R250") (pin "1") (pinfunction "1_1") (pintype "passive"))
      (node (ref "R251") (pin "1") (pinfunction "1_1") (pintype "passive"))
      (node (ref "R252") (pin "2") (pinfunction "2_2") (pintype "passive"))
      (node (ref "R256") (pin "1") (pinfunction "1_1") (pintype "passive"))
      (node (ref "R257") (pin "1") (pinfunction "1_1") (pintype "passive"))
      (node (ref "R258") (pin "1") (pinfunction "1_1") (pintype "passive"))
      (node (ref "R274") (pin "2") (pinfunction "2_2") (pintype "passive"))
      (node (ref "Reg202") (pin "3") (pinfunction "Gnd_3") (pintype "passive"))
      (node (ref "Reg202") (pin "6") (pinfunction "HTSNK_6") (pintype "passive"))
      (node (ref "S205") (pin "2") (pinfunction "2_2") (pintype "passive"))
      (node (ref "TP227") (pin "1") (pinfunction "1_1") (pintype "passive"))
      (node (ref "U201") (pin "21") (pinfunction "GND_21") (pintype "power_in"))
      (node (ref "U201") (pin "3") (pinfunction "GND_3") (pintype "power_in"))
      (node (ref "U201") (pin "5") (pinfunction "GND_5") (pintype "power_in"))
    )
    (net (code "41") (name "HVGND201") (class "Default")
      (node (ref "C213") (pin "1") (pinfunction "1_1") (pintype "passive"))
      (node (ref "C218") (pin "2") (pinfunction "2_2") (pintype "passive"))
      (node (ref "C219") (pin "2") (pinfunction "2_2") (pintype "passive"))
      (node (ref "C220") (pin "2") (pinfunction "2_2") (pintype "passive"))
      (node (ref "C221") (pin "2") (pinfunction "2_2") (pintype "passive"))
      (node (ref "C222") (pin "2") (pinfunction "2_2") (pintype "passive"))
      (node (ref "C230") (pin "1") (pinfunction "1_1") (pintype "passive"))
      (node (ref "C231") (pin "1") (pinfunction "1_1") (pintype "passive"))
      (node (ref "C232") (pin "1") (pinfunction "1_1") (pintype "passive"))
      (node (ref "C233") (pin "1") (pinfunction "1_1") (pintype "passive"))
      (node (ref "C234") (pin "2") (pinfunction "2_2") (pintype "passive"))
      (node (ref "C235") (pin "2") (pinfunction "2_2") (pintype "passive"))
      (node (ref "C236") (pin "2") (pinfunction "2_2") (pintype "passive"))
      (node (ref "C237") (pin "2") (pinfunction "2_2") (pintype "passive"))
      (node (ref "C238") (pin "2") (pinfunction "2_2") (pintype "passive"))
      (node (ref "C242") (pin "2") (pinfunction "2_2") (pintype "passive"))
      (node (ref "C243") (pin "2") (pinfunction "2_2") (pintype "passive"))
      (node (ref "C299") (pin "2") (pinfunction "2_2") (pintype "passive"))
      (node (ref "L205") (pin "1") (pinfunction "1_1") (pintype "passive"))
      (node (ref "MOS205") (pin "3") (pinfunction "S_3") (pintype "passive"))
      (node (ref "MOS206") (pin "1") (pinfunction "S_1") (pintype "passive"))
      (node (ref "R261") (pin "2") (pinfunction "2_2") (pintype "passive"))
      (node (ref "R263a") (pin "2") (pinfunction "2_2") (pintype "passive"))
      (node (ref "R265") (pin "2") (pinfunction "2_2") (pintype "passive"))
      (node (ref "R275") (pin "2") (pinfunction "2_2") (pintype "passive"))
      (node (ref "R276") (pin "1") (pinfunction "1_1") (pintype "passive"))
      (node (ref "T201") (pin "4") (pinfunction "Sec3-_4") (pintype "passive"))
      (node (ref "TP226") (pin "1") (pinfunction "1_1") (pintype "passive"))
      (node (ref "U204") (pin "1") (pinfunction "GND_1") (pintype "passive"))
      (node (ref "U205") (pin "1") (pinfunction "GND_1") (pintype "passive"))
      (node (ref "U206") (pin "5") (pinfunction "GND_5") (pintype "passive"))
      (node (ref "U207") (pin "7") (pinfunction "GND_7") (pintype "power_in"))
    )
    (net (code "42") (name "Net-(C217-Pad2)") (class "Default")
      (node (ref "C217") (pin "2") (pinfunction "2_2") (pintype "passive"))
      (node (ref "L203") (pin "1") (pinfunction "1_1") (pintype "passive"))
      (node (ref "R273") (pin "2") (pinfunction "2_2") (pintype "passive"))
    )
    (net (code "43") (name "Net-(D201-A)") (class "Default")
      (node (ref "C211") (pin "1") (pinfunction "1_1") (pintype "passive"))
      (node (ref "D201") (pin "3") (pinfunction "A_3") (pintype "passive"))
      (node (ref "T201") (pin "1") (pinfunction "Sec1+_1") (pintype "passive"))
    )
    (net (code "44") (name "Net-(EL201-Pad1)") (class "Default")
      (node (ref "EL201") (pin "1") (pinfunction "1_1") (pintype "passive"))
      (node (ref "L203") (pin "2") (pinfunction "2_2") (pintype "passive"))
    )
    (net (code "45") (name "Net-(L202-Pad1)") (class "Default")
      (node (ref "L202") (pin "1") (pinfunction "1_1") (pintype "passive"))
      (node (ref "R260") (pin "1") (pinfunction "1_1") (pintype "passive"))
      (node (ref "R275") (pin "1") (pinfunction "1_1") (pintype "passive"))
    )
    (net (code "46") (name "Net-(L204-Pad1)") (class "Default")
      (node (ref "L204") (pin "1") (pinfunction "1_1") (pintype "passive"))
      (node (ref "R262") (pin "1") (pinfunction "1_1") (pintype "passive"))
    )
    (net (code "47") (name "Net-(MOS201A-D)") (class "Default")
      (node (ref "MOS201") (pin "6") (pinfunction "D_6") (pintype "passive"))
      (node (ref "R246") (pin "2") (pinfunction "2_2") (pintype "passive"))
    )
    (net (code "48") (name "Net-(MOS201B-D)") (class "Default")
      (node (ref "MOS201") (pin "3") (pinfunction "D_3") (pintype "passive"))
      (node (ref "R247") (pin "2") (pinfunction "2_2") (pintype "passive"))
    )
    (net (code "49") (name "Net-(MOS202A-D)") (class "Default")
      (node (ref "MOS202") (pin "6") (pinfunction "D_6") (pintype "passive"))
      (node (ref "R248") (pin "2") (pinfunction "2_2") (pintype "passive"))
    )
    (net (code "50") (name "Net-(MOS202B-D)") (class "Default")
      (node (ref "MOS202") (pin "3") (pinfunction "D_3") (pintype "passive"))
      (node (ref "R253") (pin "2") (pinfunction "2_2") (pintype "passive"))
    )
    (net (code "51") (name "Net-(MOS203A-D)") (class "Default")
      (node (ref "MOS203") (pin "6") (pinfunction "D_6") (pintype "passive"))
      (node (ref "R254") (pin "2") (pinfunction "2_2") (pintype "passive"))
    )
    (net (code "52") (name "Net-(MOS203B-D)") (class "Default")
      (node (ref "MOS203") (pin "3") (pinfunction "D_3") (pintype "passive"))
      (node (ref "R255") (pin "2") (pinfunction "2_2") (pintype "passive"))
    )
    (net (code "53") (name "Net-(MOS204-D)") (class "Default")
      (node (ref "C211") (pin "2") (pinfunction "2_2") (pintype "passive"))
      (node (ref "MOS204") (pin "1") (pinfunction "D_1") (pintype "passive"))
      (node (ref "T201") (pin "10") (pinfunction "Pri+_10") (pintype "passive"))
    )
    (net (code "54") (name "Net-(MOS204-G)") (class "Default")
      (node (ref "L202") (pin "2") (pinfunction "2_2") (pintype "passive"))
      (node (ref "MOS204") (pin "2") (pinfunction "G_2") (pintype "passive"))
      (node (ref "TP216") (pin "1") (pinfunction "1_1") (pintype "passive"))
    )
    (net (code "55") (name "Net-(MOS205-D)") (class "Default")
      (node (ref "C217") (pin "1") (pinfunction "1_1") (pintype "passive"))
      (node (ref "EL201") (pin "2") (pinfunction "2_2") (pintype "passive"))
      (node (ref "MOS205") (pin "1") (pinfunction "D_1") (pintype "passive"))
    )
    (net (code "56") (name "Net-(MOS205-G)") (class "Default")
      (node (ref "L204") (pin "2") (pinfunction "2_2") (pintype "passive"))
      (node (ref "MOS205") (pin "2") (pinfunction "G_2") (pintype "passive"))
      (node (ref "R276") (pin "2") (pinfunction "2_2") (pintype "passive"))
    )
    (net (code "57") (name "Net-(MOS206A-D)") (class "Default")
      (node (ref "MOS206") (pin "6") (pinfunction "D_6") (pintype "passive"))
      (node (ref "TP223") (pin "1") (pinfunction "1_1") (pintype "passive"))
      (node (ref "U206") (pin "4") (pinfunction "Osc_4") (pintype "passive"))
      (node (ref "U207") (pin "2") (pinfunction "Y_2") (pintype "output"))
    )
    (net (code "58") (name "Net-(R263a-Pad1)") (class "Default")
      (node (ref "R263a") (pin "1") (pinfunction "1_1") (pintype "passive"))
      (node (ref "R263b") (pin "2") (pinfunction "2_2") (pintype "passive"))
    )
    (net (code "59") (name "Net-(U201-AREF)") (class "Default")
      (node (ref "C208") (pin "2") (pinfunction "2_2") (pintype "passive"))
      (node (ref "U201") (pin "20") (pinfunction "AREF_20") (pintype "passive"))
    )
    (net (code "60") (name "Net-(U201-AVCC)") (class "Default")
      (node (ref "C209") (pin "2") (pinfunction "2_2") (pintype "passive"))
      (node (ref "L201") (pin "1") (pinfunction "1_1") (pintype "passive"))
      (node (ref "U201") (pin "18") (pinfunction "AVCC_18") (pintype "power_in"))
    )
    (net (code "61") (name "Net-(U204-CONT)") (class "Default")
      (node (ref "C230") (pin "2") (pinfunction "2_2") (pintype "passive"))
      (node (ref "U204") (pin "5") (pinfunction "CONT_5") (pintype "passive"))
    )
    (net (code "62") (name "Net-(U204-Dis)") (class "Default")
      (node (ref "R267") (pin "2") (pinfunction "2_2") (pintype "passive"))
      (node (ref "R271") (pin "1") (pinfunction "1_1") (pintype "passive"))
      (node (ref "U204") (pin "7") (pinfunction "Dis_7") (pintype "passive"))
    )
    (net (code "63") (name "Net-(U204-TRIG)") (class "Default")
      (node (ref "C232") (pin "2") (pinfunction "2_2") (pintype "passive"))
      (node (ref "R271") (pin "2") (pinfunction "2_2") (pintype "passive"))
      (node (ref "U204") (pin "2") (pinfunction "TRIG_2") (pintype "passive"))
      (node (ref "U204") (pin "6") (pinfunction "Thr_6") (pintype "passive"))
    )
    (net (code "64") (name "Net-(U205-CONT)") (class "Default")
      (node (ref "C231") (pin "2") (pinfunction "2_2") (pintype "passive"))
      (node (ref "U205") (pin "5") (pinfunction "CONT_5") (pintype "passive"))
    )
    (net (code "65") (name "Net-(U205-Dis)") (class "Default")
      (node (ref "R268") (pin "2") (pinfunction "2_2") (pintype "passive"))
      (node (ref "R272") (pin "1") (pinfunction "1_1") (pintype "passive"))
      (node (ref "U205") (pin "7") (pinfunction "Dis_7") (pintype "passive"))
    )
    (net (code "66") (name "Net-(U205-TRIG)") (class "Default")
      (node (ref "C233") (pin "2") (pinfunction "2_2") (pintype "passive"))
      (node (ref "R272") (pin "2") (pinfunction "2_2") (pintype "passive"))
      (node (ref "U205") (pin "2") (pinfunction "TRIG_2") (pintype "passive"))
      (node (ref "U205") (pin "6") (pinfunction "Thr_6") (pintype "passive"))
    )
    (net (code "67") (name "Net-(U206-Comp)") (class "Default")
      (node (ref "C229") (pin "1") (pinfunction "1_1") (pintype "passive"))
      (node (ref "U206") (pin "1") (pinfunction "Comp_1") (pintype "passive"))
    )
    (net (code "68") (name "Net-(U206-Vref)") (class "Default")
      (node (ref "R265") (pin "1") (pinfunction "1_1") (pintype "passive"))
      (node (ref "R266") (pin "1") (pinfunction "1_1") (pintype "passive"))
      (node (ref "U206") (pin "8") (pinfunction "Vref_8") (pintype "passive"))
    )
    (net (code "69") (name "VCC201") (class "Default")
      (node (ref "C205") (pin "2") (pinfunction "2_2") (pintype "passive"))
      (node (ref "C206") (pin "2") (pinfunction "2_2") (pintype "passive"))
      (node (ref "C207") (pin "2") (pinfunction "2_2") (pintype "passive"))
      (node (ref "C210") (pin "2") (pinfunction "2_2") (pintype "passive"))
      (node (ref "C214") (pin "2") (pinfunction "2_2") (pintype "passive"))
      (node (ref "C218") (pin "1") (pinfunction "1_1") (pintype "passive"))
      (node (ref "C220") (pin "1") (pinfunction "1_1") (pintype "passive"))
      (node (ref "C226") (pin "2") (pinfunction "2_2") (pintype "passive"))
      (node (ref "C227") (pin "2") (pinfunction "2_2") (pintype "passive"))
      (node (ref "C228") (pin "2") (pinfunction "2_2") (pintype "passive"))
      (node (ref "C234") (pin "1") (pinfunction "1_1") (pintype "passive"))
      (node (ref "C235") (pin "1") (pinfunction "1_1") (pintype "passive"))
      (node (ref "C236") (pin "1") (pinfunction "1_1") (pintype "passive"))
      (node (ref "C237") (pin "1") (pinfunction "1_1") (pintype "passive"))
      (node (ref "C238") (pin "1") (pinfunction "1_1") (pintype "passive"))
      (node (ref "C242") (pin "1") (pinfunction "1_1") (pintype "passive"))
      (node (ref "C243") (pin "1") (pinfunction "1_1") (pintype "passive"))
      (node (ref "C299") (pin "1") (pinfunction "1_1") (pintype "passive"))
      (node (ref "I201") (pin "1") (pinfunction "1_1") (pintype "passive"))
      (node (ref "I225") (pin "1") (pinfunction "1_1") (pintype "passive"))
      (node (ref "I228") (pin "1") (pinfunction "1_1") (pintype "passive"))
      (node (ref "ISP201") (pin "2") (pinfunction "2_2") (pintype "passive"))
      (node (ref "L201") (pin "2") (pinfunction "2_2") (pintype "passive"))
      (node (ref "Opt_Rx_201") (pin "3") (pinfunction "VCC_3") (pintype "passive"))
      (node (ref "Opt_Tx_201") (pin "2") (pinfunction "VDD_2") (pintype "passive"))
      (node (ref "R266") (pin "2") (pinfunction "2_2") (pintype "passive"))
      (node (ref "R267") (pin "1") (pinfunction "1_1") (pintype "passive"))
      (node (ref "R268") (pin "1") (pinfunction "1_1") (pintype "passive"))
      (node (ref "R269") (pin "2") (pinfunction "2_2") (pintype "passive"))
      (node (ref "R270") (pin "2") (pinfunction "2_2") (pintype "passive"))
      (node (ref "R277") (pin "2") (pinfunction "2_2") (pintype "passive"))
      (node (ref "Reg202") (pin "2") (pinfunction "Vout_2") (pintype "passive"))
      (node (ref "U201") (pin "4") (pinfunction "VCC_4") (pintype "power_in"))
      (node (ref "U201") (pin "6") (pinfunction "VCC_6") (pintype "power_in"))
      (node (ref "U204") (pin "4") (pinfunction "Reset_4") (pintype "passive"))
      (node (ref "U204") (pin "8") (pinfunction "VCC_8") (pintype "passive"))
      (node (ref "U205") (pin "4") (pinfunction "Reset_4") (pintype "passive"))
      (node (ref "U205") (pin "8") (pinfunction "VCC_8") (pintype "passive"))
      (node (ref "U206") (pin "7") (pinfunction "Vin_7") (pintype "passive"))
      (node (ref "U207") (pin "14") (pinfunction "VCC_14") (pintype "power_in"))
    )
    (net (code "70") (name "unconnected-(Reg202-NR{slash}Adj-Pad4)") (class "Default")
      (node (ref "Reg202") (pin "4") (pinfunction "NR/Adj_4") (pintype "passive+no_connect"))
    )
    (net (code "71") (name "unconnected-(T201-Sec2+-Pad2)") (class "Default")
      (node (ref "T201") (pin "2") (pinfunction "Sec2+_2") (pintype "passive+no_connect"))
    )
    (net (code "72") (name "unconnected-(T201-Sec3+-Pad3)") (class "Default")
      (node (ref "T201") (pin "3") (pinfunction "Sec3+_3") (pintype "passive+no_connect"))
    )
    (net (code "73") (name "unconnected-(U201-ADC6-Pad19)") (class "Default")
      (node (ref "U201") (pin "19") (pinfunction "ADC6_19") (pintype "input"))
    )
  )
)
